# esp-socket-3.net
KiCad netlist of a schematic drawn in EAGLE
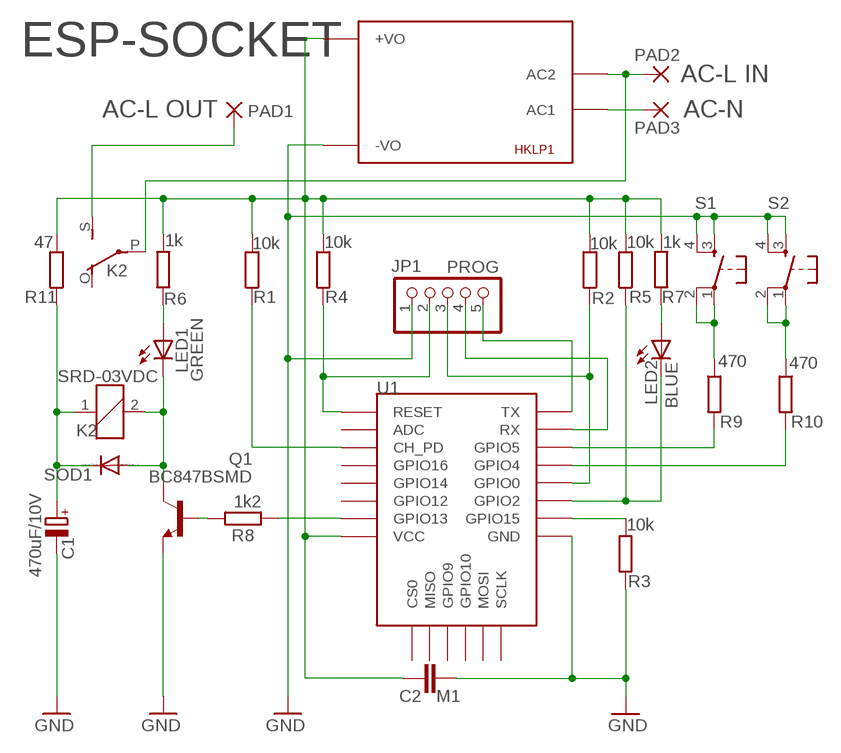
[diagram p0: schematic, sheet 1]

(export (version "E")
  (design (tool "Eeschema 10.0.6"))
  (components
    (comp (ref "C1")
      (value "470uF/10V")
      (footprint "eagle-import:E3,5-8")
      (libsource (lib "eagle-import") (part "CPOL-EUE3.5-8"))
    )
    (comp (ref "C2")
      (value "M1")
      (footprint "eagle-import:C1206")
      (libsource (lib "eagle-import") (part "C-EUC1206"))
    )
    (comp (ref "HKLP1")
      (value "HKLPM01")
      (footprint "eagle-import:HKLPM01")
      (libsource (lib "eagle-import") (part "HKLPM01"))
    )
    (comp (ref "JP1")
      (value "PROG")
      (footprint "eagle-import:1X05")
      (libsource (lib "eagle-import") (part "PINHD-1X5"))
    )
    (comp (ref "K2")
      (value "SRD-03VDC")
      (footprint "eagle-import:G5L-B")
      (libsource (lib "eagle-import") (part "G5LG5L-B"))
    )
    (comp (ref "LED1")
      (value "GREEN")
      (footprint "eagle-import:LED3MM")
      (libsource (lib "eagle-import") (part "LED3MM"))
    )
    (comp (ref "LED2")
      (value "BLUE")
      (footprint "eagle-import:LED3MM")
      (libsource (lib "eagle-import") (part "LED3MM"))
    )
    (comp (ref "PAD1")
      (value "3,17/1,1")
      (footprint "eagle-import:3,17_1,1")
      (libsource (lib "eagle-import") (part "3,17/1,1"))
    )
    (comp (ref "PAD2")
      (value "3,17/1,1")
      (footprint "eagle-import:3,17_1,1")
      (libsource (lib "eagle-import") (part "3,17/1,1"))
    )
    (comp (ref "PAD3")
      (value "3,17/1,1")
      (footprint "eagle-import:3,17_1,1")
      (libsource (lib "eagle-import") (part "3,17/1,1"))
    )
    (comp (ref "Q1")
      (value "BC847BSMD")
      (footprint "eagle-import:SOT23")
      (libsource (lib "eagle-import") (part "BC847SMDB"))
    )
    (comp (ref "R1")
      (value "10k")
      (footprint "eagle-import:M1206")
      (libsource (lib "eagle-import") (part "R-EU_M1206"))
    )
    (comp (ref "R2")
      (value "10k")
      (footprint "eagle-import:M1206")
      (libsource (lib "eagle-import") (part "R-EU_M1206"))
    )
    (comp (ref "R3")
      (value "10k")
      (footprint "eagle-import:M1206")
      (libsource (lib "eagle-import") (part "R-EU_M1206"))
    )
    (comp (ref "R4")
      (value "10k")
      (footprint "eagle-import:M1206")
      (libsource (lib "eagle-import") (part "R-EU_M1206"))
    )
    (comp (ref "R5")
      (value "10k")
      (footprint "eagle-import:M1206")
      (libsource (lib "eagle-import") (part "R-EU_M1206"))
    )
    (comp (ref "R6")
      (value "1k")
      (footprint "eagle-import:M1206")
      (libsource (lib "eagle-import") (part "R-EU_M1206"))
    )
    (comp (ref "R7")
      (value "1k")
      (footprint "eagle-import:M1206")
      (libsource (lib "eagle-import") (part "R-EU_M1206"))
    )
    (comp (ref "R8")
      (value "1k2")
      (footprint "eagle-import:M1206")
      (libsource (lib "eagle-import") (part "R-EU_M1206"))
    )
    (comp (ref "R9")
      (value "470")
      (footprint "eagle-import:M1206")
      (libsource (lib "eagle-import") (part "R-EU_M1206"))
    )
    (comp (ref "R10")
      (value "470")
      (footprint "eagle-import:M1206")
      (libsource (lib "eagle-import") (part "R-EU_M1206"))
    )
    (comp (ref "R11")
      (value "47")
      (footprint "eagle-import:0207_10B")
      (libsource (lib "eagle-import") (part "R-EU_0207/10B"))
    )
    (comp (ref "S1")
      (value "DTS-6")
      (footprint "eagle-import:DTS-6")
      (libsource (lib "eagle-import") (part "DTS-6"))
    )
    (comp (ref "S2")
      (value "DTS-6")
      (footprint "eagle-import:DTS-6")
      (libsource (lib "eagle-import") (part "DTS-6"))
    )
    (comp (ref "SOD1")
      (value "DIODE-MELF-MLL41")
      (footprint "eagle-import:MELF-MLL41")
      (libsource (lib "eagle-import") (part "DIODE-MELF-MLL41"))
    )
    (comp (ref "U1")
      (value "ESP12ESMD")
      (footprint "eagle-import:ESP12E-SMD")
      (libsource (lib "eagle-import") (part "ESP12ESMD"))
    )
  )
  (nets
    (net (code "1") (name "GND") (class "Default")
      (node (ref "C1") (pin "-") (pinfunction "-_-") (pintype "passive"))
      (node (ref "C2") (pin "2") (pinfunction "2_2") (pintype "passive"))
      (node (ref "HKLP1") (pin "P$3") (pinfunction "-VO_P$3") (pintype "output"))
      (node (ref "JP1") (pin "1") (pinfunction "1_1") (pintype "passive"))
      (node (ref "Q1") (pin "2") (pinfunction "E_2") (pintype "passive"))
      (node (ref "R3") (pin "1") (pinfunction "1_1") (pintype "passive"))
      (node (ref "S1") (pin "3") (pinfunction "3_3") (pintype "passive"))
      (node (ref "S1") (pin "4") (pinfunction "4_4") (pintype "passive"))
      (node (ref "S2") (pin "3") (pinfunction "3_3") (pintype "passive"))
      (node (ref "S2") (pin "4") (pinfunction "4_4") (pintype "passive"))
      (node (ref "U1") (pin "GND") (pinfunction "GND_GND") (pintype "bidirectional"))
    )
    (net (code "2") (name "Net-(C1-Pad+)") (class "Default")
      (node (ref "C1") (pin "+") (pinfunction "+_+") (pintype "passive"))
      (node (ref "K2") (pin "1") (pinfunction "1_1") (pintype "passive"))
      (node (ref "R11") (pin "1") (pinfunction "1_1") (pintype "passive"))
      (node (ref "SOD1") (pin "C") (pinfunction "C_C") (pintype "passive"))
    )
    (net (code "3") (name "Net-(HKLP1-+VO)") (class "Default")
      (node (ref "C2") (pin "1") (pinfunction "1_1") (pintype "passive"))
      (node (ref "HKLP1") (pin "P$4") (pinfunction "+VO_P$4") (pintype "output"))
      (node (ref "R1") (pin "2") (pinfunction "2_2") (pintype "passive"))
      (node (ref "R11") (pin "2") (pinfunction "2_2") (pintype "passive"))
      (node (ref "R2") (pin "2") (pinfunction "2_2") (pintype "passive"))
      (node (ref "R4") (pin "2") (pinfunction "2_2") (pintype "passive"))
      (node (ref "R5") (pin "2") (pinfunction "2_2") (pintype "passive"))
      (node (ref "R6") (pin "2") (pinfunction "2_2") (pintype "passive"))
      (node (ref "R7") (pin "2") (pinfunction "2_2") (pintype "passive"))
      (node (ref "U1") (pin "VCC") (pinfunction "VCC_VCC") (pintype "bidirectional"))
    )
    (net (code "4") (name "Net-(HKLP1-AC1)") (class "Default")
      (node (ref "HKLP1") (pin "P$1") (pinfunction "AC1_P$1") (pintype "power_in"))
      (node (ref "PAD3") (pin "1") (pinfunction "P_1") (pintype "passive"))
    )
    (net (code "5") (name "Net-(HKLP1-AC2)") (class "Default")
      (node (ref "HKLP1") (pin "P$2") (pinfunction "AC2_P$2") (pintype "power_in"))
      (node (ref "K2") (pin "P") (pinfunction "P_P") (pintype "passive"))
      (node (ref "PAD2") (pin "1") (pinfunction "P_1") (pintype "passive"))
    )
    (net (code "6") (name "Net-(JP1-Pad2)") (class "Default")
      (node (ref "JP1") (pin "2") (pinfunction "2_2") (pintype "passive"))
      (node (ref "R4") (pin "1") (pinfunction "1_1") (pintype "passive"))
      (node (ref "U1") (pin "RESET") (pinfunction "RESET_RESET") (pintype "bidirectional"))
    )
    (net (code "7") (name "Net-(JP1-Pad3)") (class "Default")
      (node (ref "JP1") (pin "3") (pinfunction "3_3") (pintype "passive"))
      (node (ref "R2") (pin "1") (pinfunction "1_1") (pintype "passive"))
      (node (ref "U1") (pin "GPIO0") (pinfunction "GPIO0_GPIO0") (pintype "bidirectional"))
    )
    (net (code "8") (name "Net-(LED1-C)") (class "Default")
      (node (ref "K2") (pin "2") (pinfunction "2_2") (pintype "passive"))
      (node (ref "LED1") (pin "K") (pinfunction "C_K") (pintype "passive"))
      (node (ref "Q1") (pin "3") (pinfunction "C_3") (pintype "passive"))
      (node (ref "SOD1") (pin "A") (pinfunction "A_A") (pintype "passive"))
    )
    (net (code "9") (name "Net-(LED1-PadA)") (class "Default")
      (node (ref "LED1") (pin "A") (pinfunction "A_A") (pintype "passive"))
      (node (ref "R6") (pin "1") (pinfunction "1_1") (pintype "passive"))
    )
    (net (code "10") (name "Net-(LED2-C)") (class "Default")
      (node (ref "LED2") (pin "K") (pinfunction "C_K") (pintype "passive"))
      (node (ref "R5") (pin "1") (pinfunction "1_1") (pintype "passive"))
      (node (ref "U1") (pin "GPIO2") (pinfunction "GPIO2_GPIO2") (pintype "bidirectional"))
    )
    (net (code "11") (name "Net-(LED2-PadA)") (class "Default")
      (node (ref "LED2") (pin "A") (pinfunction "A_A") (pintype "passive"))
      (node (ref "R7") (pin "1") (pinfunction "1_1") (pintype "passive"))
    )
    (net (code "12") (name "Net-(PAD1-P)") (class "Default")
      (node (ref "K2") (pin "S") (pinfunction "S_S") (pintype "passive"))
      (node (ref "PAD1") (pin "1") (pinfunction "P_1") (pintype "passive"))
    )
    (net (code "13") (name "Net-(Q1-B)") (class "Default")
      (node (ref "Q1") (pin "1") (pinfunction "B_1") (pintype "passive"))
      (node (ref "R8") (pin "2") (pinfunction "2_2") (pintype "passive"))
    )
    (net (code "14") (name "Net-(R1-Pad1)") (class "Default")
      (node (ref "R1") (pin "1") (pinfunction "1_1") (pintype "passive"))
      (node (ref "U1") (pin "CH_PD") (pinfunction "CH_PD_CH_PD") (pintype "bidirectional"))
    )
    (net (code "15") (name "Net-(R3-Pad2)") (class "Default")
      (node (ref "R3") (pin "2") (pinfunction "2_2") (pintype "passive"))
      (node (ref "U1") (pin "GPIO15") (pinfunction "GPIO15_GPIO15") (pintype "bidirectional"))
    )
    (net (code "16") (name "Net-(R8-Pad1)") (class "Default")
      (node (ref "R8") (pin "1") (pinfunction "1_1") (pintype "passive"))
      (node (ref "U1") (pin "GPIO13") (pinfunction "GPIO13_GPIO13") (pintype "bidirectional"))
    )
    (net (code "17") (name "Net-(R9-Pad1)") (class "Default")
      (node (ref "R9") (pin "1") (pinfunction "1_1") (pintype "passive"))
      (node (ref "S1") (pin "1") (pinfunction "1_1") (pintype "passive"))
      (node (ref "S1") (pin "2") (pinfunction "2_2") (pintype "passive"))
    )
    (net (code "18") (name "Net-(R9-Pad2)") (class "Default")
      (node (ref "R9") (pin "2") (pinfunction "2_2") (pintype "passive"))
      (node (ref "U1") (pin "GPIO5") (pinfunction "GPIO5_GPIO5") (pintype "bidirectional"))
    )
    (net (code "19") (name "Net-(R10-Pad1)") (class "Default")
      (node (ref "R10") (pin "1") (pinfunction "1_1") (pintype "passive"))
      (node (ref "S2") (pin "1") (pinfunction "1_1") (pintype "passive"))
      (node (ref "S2") (pin "2") (pinfunction "2_2") (pintype "passive"))
    )
    (net (code "20") (name "Net-(R10-Pad2)") (class "Default")
      (node (ref "R10") (pin "2") (pinfunction "2_2") (pintype "passive"))
      (node (ref "U1") (pin "GPIO4") (pinfunction "GPIO4_GPIO4") (pintype "bidirectional"))
    )
    (net (code "21") (name "Net-(U1-RX)") (class "Default")
      (node (ref "JP1") (pin "4") (pinfunction "4_4") (pintype "passive"))
      (node (ref "U1") (pin "RXD0") (pinfunction "RX_RXD0") (pintype "bidirectional"))
    )
    (net (code "22") (name "Net-(U1-TX)") (class "Default")
      (node (ref "JP1") (pin "5") (pinfunction "5_5") (pintype "passive"))
      (node (ref "U1") (pin "TXD0") (pinfunction "TX_TXD0") (pintype "bidirectional"))
    )
    (net (code "23") (name "unconnected-(K2-PadO)") (class "Default")
      (node (ref "K2") (pin "O") (pinfunction "O_O") (pintype "passive"))
    )
    (net (code "24") (name "unconnected-(U1-PadADC)") (class "Default")
      (node (ref "U1") (pin "ADC") (pinfunction "ADC_ADC") (pintype "bidirectional"))
    )
    (net (code "25") (name "unconnected-(U1-PadCS0)") (class "Default")
      (node (ref "U1") (pin "CS0") (pinfunction "CS0_CS0") (pintype "bidirectional"))
    )
    (net (code "26") (name "unconnected-(U1-PadGPIO9)") (class "Default")
      (node (ref "U1") (pin "GPIO9") (pinfunction "GPIO9_GPIO9") (pintype "bidirectional"))
    )
    (net (code "27") (name "unconnected-(U1-PadGPIO10)") (class "Default")
      (node (ref "U1") (pin "GPIO10") (pinfunction "GPIO10_GPIO10") (pintype "bidirectional"))
    )
    (net (code "28") (name "unconnected-(U1-PadGPIO12)") (class "Default")
      (node (ref "U1") (pin "GPIO12") (pinfunction "GPIO12_GPIO12") (pintype "bidirectional"))
    )
    (net (code "29") (name "unconnected-(U1-PadGPIO14)") (class "Default")
      (node (ref "U1") (pin "GPIO14") (pinfunction "GPIO14_GPIO14") (pintype "bidirectional"))
    )
    (net (code "30") (name "unconnected-(U1-PadGPIO16)") (class "Default")
      (node (ref "U1") (pin "GPIO16") (pinfunction "GPIO16_GPIO16") (pintype "bidirectional"))
    )
    (net (code "31") (name "unconnected-(U1-PadMISO)") (class "Default")
      (node (ref "U1") (pin "MISO") (pinfunction "MISO_MISO") (pintype "bidirectional"))
    )
    (net (code "32") (name "unconnected-(U1-PadMOSI)") (class "Default")
      (node (ref "U1") (pin "MOSI") (pinfunction "MOSI_MOSI") (pintype "bidirectional"))
    )
    (net (code "33") (name "unconnected-(U1-PadSCLK)") (class "Default")
      (node (ref "U1") (pin "SCLK") (pinfunction "SCLK_SCLK") (pintype "bidirectional"))
    )
  )
)
